# HUZZAH_ESP8266.net
KiCad netlist of a schematic drawn in EAGLE
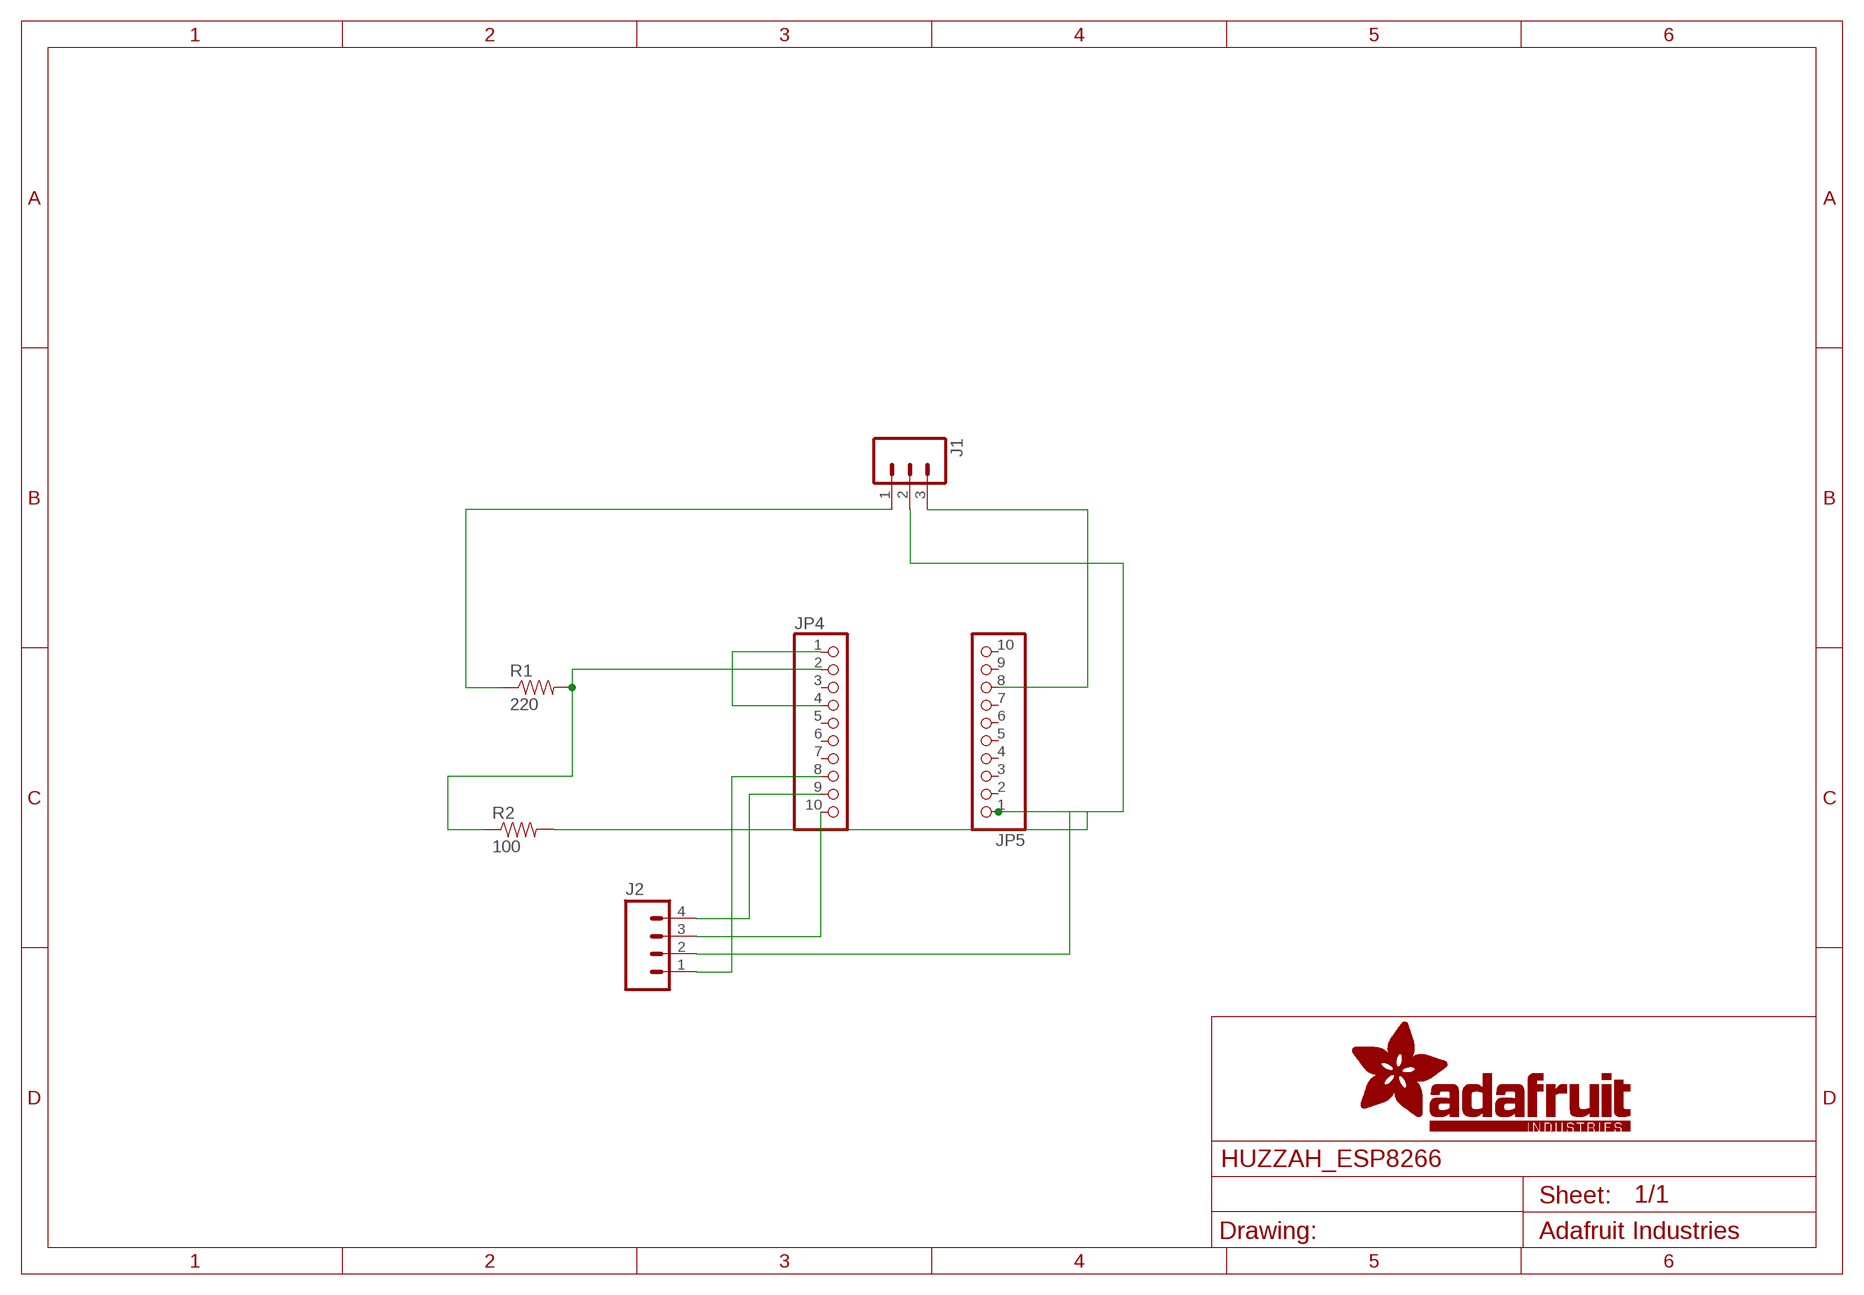
[diagram p0: schematic, sheet 1]

(export (version "E")
  (design (tool "Eeschema 10.0.6"))
  (components
    (comp (ref "J1")
      (value "M031X03_NO_SILK")
      (footprint "eagle-import:1X03_NO_SILK")
      (libsource (lib "eagle-import") (part "M031X03_NO_SILK"))
    )
    (comp (ref "J2")
      (value "M041X04_NO_SILK")
      (footprint "eagle-import:1X04_NO_SILK")
      (libsource (lib "eagle-import") (part "M041X04_NO_SILK"))
    )
    (comp (ref "JP4")
      (value "HEADER-1X1070MIL")
      (footprint "eagle-import:1X10_ROUND70")
      (libsource (lib "eagle-import") (part "HEADER-1X1070MIL"))
    )
    (comp (ref "JP5")
      (value "HEADER-1X1070MIL")
      (footprint "eagle-import:1X10_ROUND70")
      (libsource (lib "eagle-import") (part "HEADER-1X1070MIL"))
    )
    (comp (ref "R1")
      (value "220")
      (footprint "eagle-import:AXIAL-0.3")
      (libsource (lib "eagle-import") (part "100OHM-1/4W-1%(PTH)"))
    )
    (comp (ref "R2")
      (value "100")
      (footprint "eagle-import:AXIAL-0.3")
      (libsource (lib "eagle-import") (part "100OHM-1/4W-1%(PTH)"))
    )
  )
  (nets
    (net (code "1") (name "Net-(J1-Pad3)") (class "Default")
      (node (ref "J1") (pin "3") (pinfunction "3_3") (pintype "passive"))
      (node (ref "JP5") (pin "8") (pinfunction "8_8") (pintype "passive"))
    )
    (net (code "2") (name "Net-(J2-Pad1)") (class "Default")
      (node (ref "J2") (pin "1") (pinfunction "1_1") (pintype "passive"))
      (node (ref "JP4") (pin "8") (pinfunction "8_8") (pintype "passive"))
    )
    (net (code "3") (name "Net-(J2-Pad3)") (class "Default")
      (node (ref "J2") (pin "3") (pinfunction "3_3") (pintype "passive"))
      (node (ref "JP4") (pin "10") (pinfunction "10_10") (pintype "passive"))
    )
    (net (code "4") (name "Net-(J2-Pad4)") (class "Default")
      (node (ref "J2") (pin "4") (pinfunction "4_4") (pintype "passive"))
      (node (ref "JP4") (pin "9") (pinfunction "9_9") (pintype "passive"))
    )
    (net (code "5") (name "Net-(JP4-Pad1)") (class "Default")
      (node (ref "JP4") (pin "1") (pinfunction "1_1") (pintype "passive"))
      (node (ref "JP4") (pin "4") (pinfunction "4_4") (pintype "passive"))
    )
    (net (code "6") (name "Net-(R1-1)") (class "Default")
      (node (ref "J1") (pin "1") (pinfunction "1_1") (pintype "passive"))
      (node (ref "R1") (pin "P$1") (pinfunction "1_P$1") (pintype "passive"))
    )
    (net (code "7") (name "Net-(R1-2)") (class "Default")
      (node (ref "JP4") (pin "2") (pinfunction "2_2") (pintype "passive"))
      (node (ref "R1") (pin "P$2") (pinfunction "2_P$2") (pintype "passive"))
      (node (ref "R2") (pin "P$1") (pinfunction "1_P$1") (pintype "passive"))
    )
    (net (code "8") (name "Net-(R2-2)") (class "Default")
      (node (ref "J1") (pin "2") (pinfunction "2_2") (pintype "passive"))
      (node (ref "J2") (pin "2") (pinfunction "2_2") (pintype "passive"))
      (node (ref "JP5") (pin "1") (pinfunction "1_1") (pintype "passive"))
      (node (ref "R2") (pin "P$2") (pinfunction "2_P$2") (pintype "passive"))
    )
    (net (code "9") (name "unconnected-(JP4-Pad3)") (class "Default")
      (node (ref "JP4") (pin "3") (pinfunction "3_3") (pintype "passive"))
    )
    (net (code "10") (name "unconnected-(JP4-Pad5)") (class "Default")
      (node (ref "JP4") (pin "5") (pinfunction "5_5") (pintype "passive"))
    )
    (net (code "11") (name "unconnected-(JP4-Pad6)") (class "Default")
      (node (ref "JP4") (pin "6") (pinfunction "6_6") (pintype "passive"))
    )
    (net (code "12") (name "unconnected-(JP4-Pad7)") (class "Default")
      (node (ref "JP4") (pin "7") (pinfunction "7_7") (pintype "passive"))
    )
    (net (code "13") (name "unconnected-(JP5-Pad2)") (class "Default")
      (node (ref "JP5") (pin "2") (pinfunction "2_2") (pintype "passive"))
    )
    (net (code "14") (name "unconnected-(JP5-Pad3)") (class "Default")
      (node (ref "JP5") (pin "3") (pinfunction "3_3") (pintype "passive"))
    )
    (net (code "15") (name "unconnected-(JP5-Pad4)") (class "Default")
      (node (ref "JP5") (pin "4") (pinfunction "4_4") (pintype "passive"))
    )
    (net (code "16") (name "unconnected-(JP5-Pad5)") (class "Default")
      (node (ref "JP5") (pin "5") (pinfunction "5_5") (pintype "passive"))
    )
    (net (code "17") (name "unconnected-(JP5-Pad6)") (class "Default")
      (node (ref "JP5") (pin "6") (pinfunction "6_6") (pintype "passive"))
    )
    (net (code "18") (name "unconnected-(JP5-Pad7)") (class "Default")
      (node (ref "JP5") (pin "7") (pinfunction "7_7") (pintype "passive"))
    )
    (net (code "19") (name "unconnected-(JP5-Pad9)") (class "Default")
      (node (ref "JP5") (pin "9") (pinfunction "9_9") (pintype "passive"))
    )
    (net (code "20") (name "unconnected-(JP5-Pad10)") (class "Default")
      (node (ref "JP5") (pin "10") (pinfunction "10_10") (pintype "passive"))
    )
  )
)
